# Welder_HMI.net
KiCad netlist of a schematic drawn in EAGLE
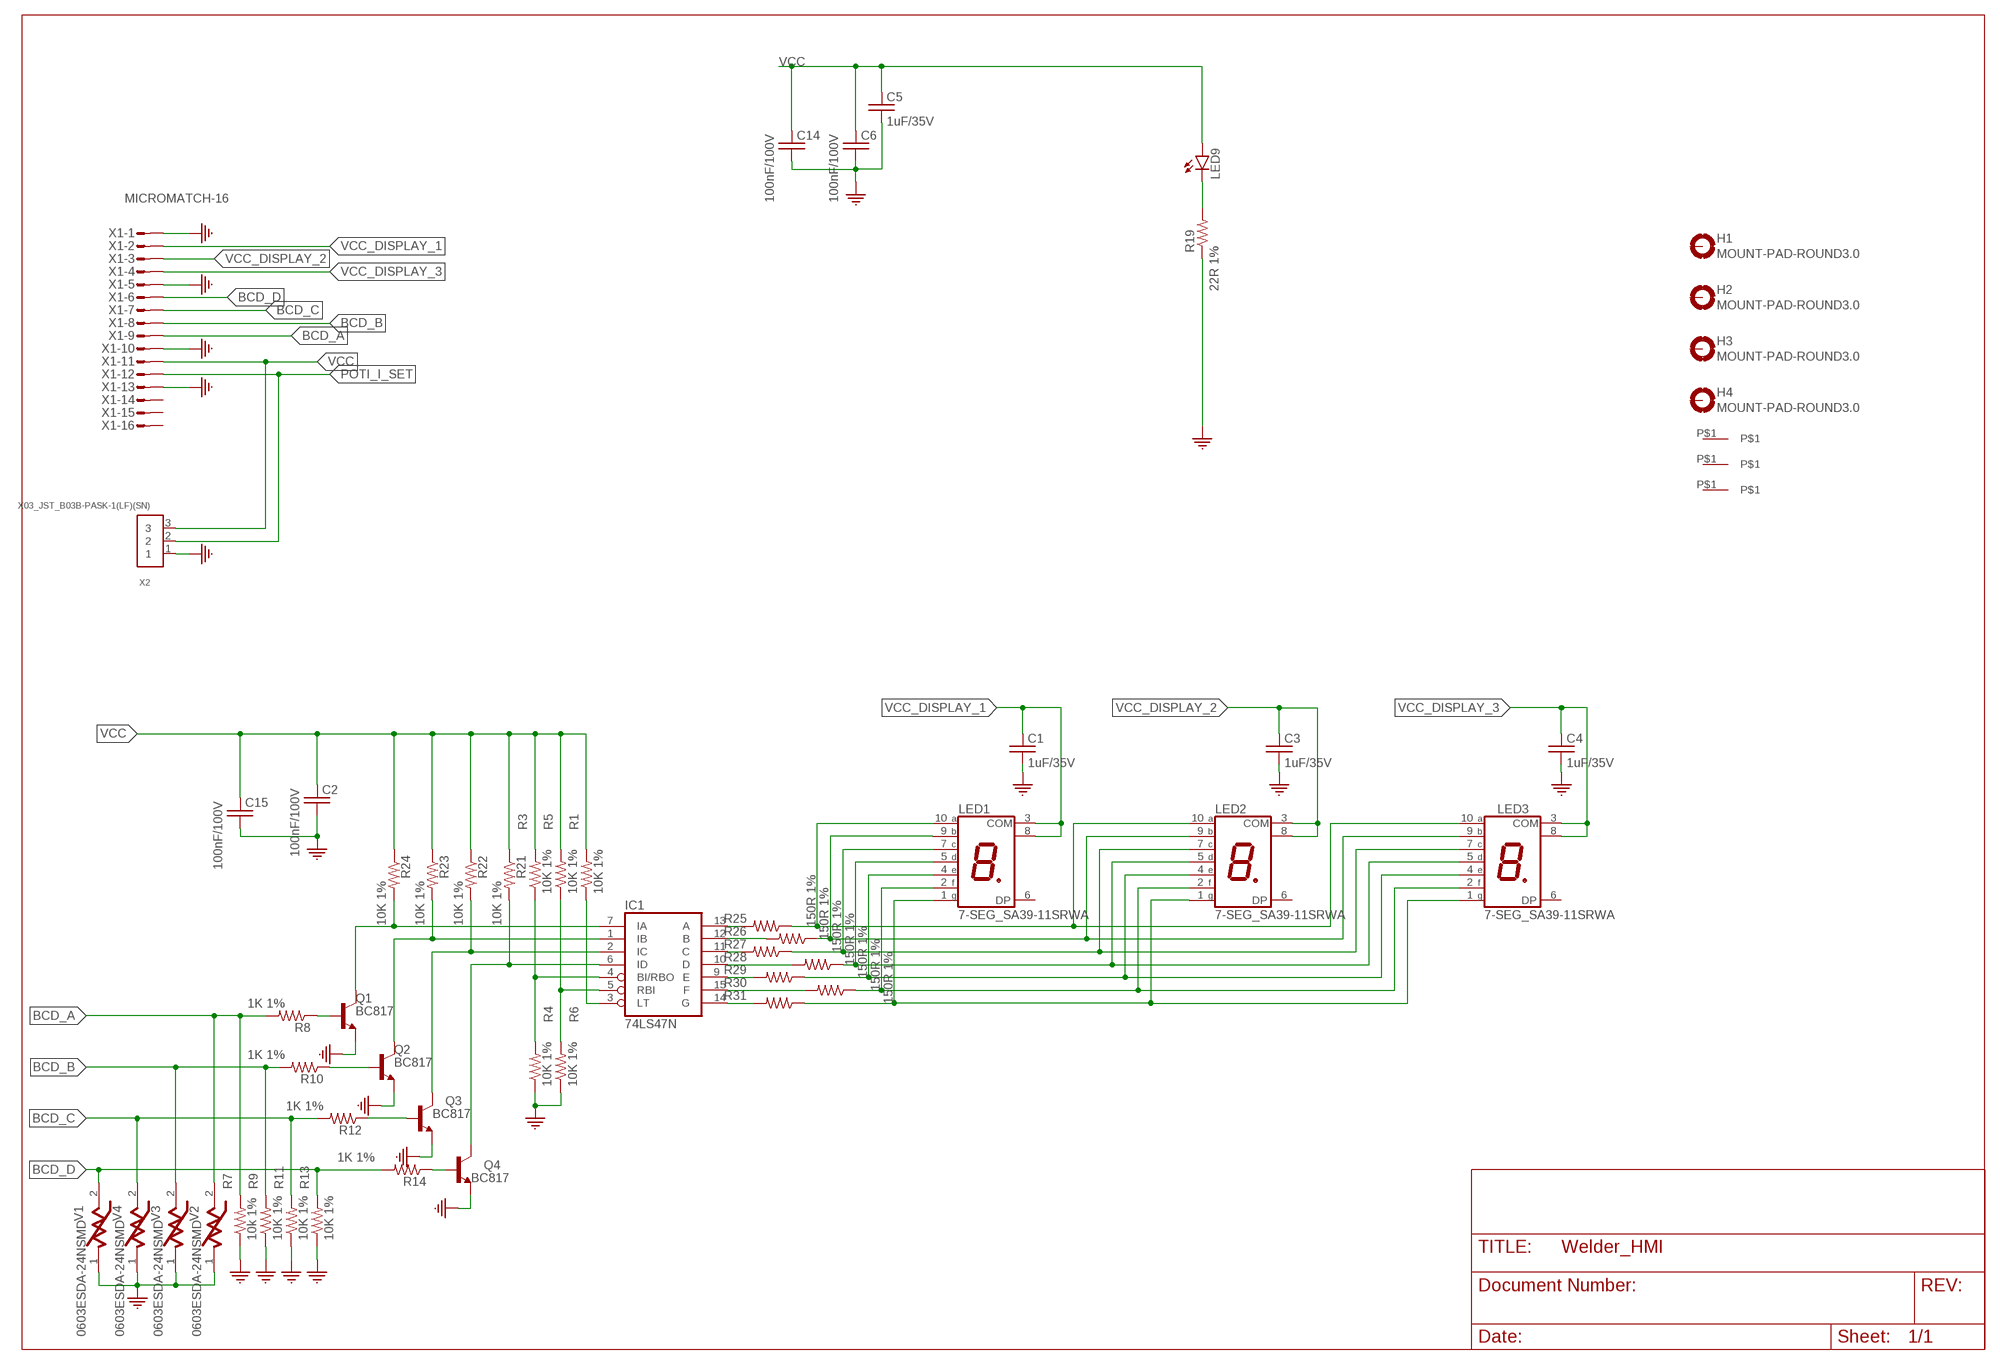
[diagram p0: schematic, sheet 1]

(export (version "E")
  (design (tool "Eeschema 10.0.6"))
  (components
    (comp (ref "C1")
      (value "1uF/35V")
      (footprint "eagle-import:EIA0603")
      (libsource (lib "eagle-import") (part "C_0603EIA0603"))
    )
    (comp (ref "C2")
      (value "100nF/100V")
      (footprint "eagle-import:EIA0603")
      (libsource (lib "eagle-import") (part "C_0603EIA0603"))
    )
    (comp (ref "C3")
      (value "1uF/35V")
      (footprint "eagle-import:EIA0603")
      (libsource (lib "eagle-import") (part "C_0603EIA0603"))
    )
    (comp (ref "C4")
      (value "1uF/35V")
      (footprint "eagle-import:EIA0603")
      (libsource (lib "eagle-import") (part "C_0603EIA0603"))
    )
    (comp (ref "C5")
      (value "1uF/35V")
      (footprint "eagle-import:EIA0603")
      (libsource (lib "eagle-import") (part "C_0603EIA0603"))
    )
    (comp (ref "C6")
      (value "100nF/100V")
      (footprint "eagle-import:EIA0603")
      (libsource (lib "eagle-import") (part "C_0603EIA0603"))
    )
    (comp (ref "C14")
      (value "100nF/100V")
      (footprint "eagle-import:EIA0603")
      (libsource (lib "eagle-import") (part "C_0603EIA0603"))
    )
    (comp (ref "C15")
      (value "100nF/100V")
      (footprint "eagle-import:EIA0603")
      (libsource (lib "eagle-import") (part "C_0603EIA0603"))
    )
    (comp (ref "FID1")
      (value "FIDUCIAL")
      (footprint "eagle-import:FIDUCIAL")
      (libsource (lib "eagle-import") (part "FIDUCIAL"))
    )
    (comp (ref "FID2")
      (value "FIDUCIAL")
      (footprint "eagle-import:FIDUCIAL")
      (libsource (lib "eagle-import") (part "FIDUCIAL"))
    )
    (comp (ref "FID3")
      (value "FIDUCIAL")
      (footprint "eagle-import:FIDUCIAL")
      (libsource (lib "eagle-import") (part "FIDUCIAL"))
    )
    (comp (ref "H1")
      (value "MOUNT-PAD-ROUND3.0")
      (footprint "eagle-import:3,0-PAD")
      (libsource (lib "eagle-import") (part "MOUNT-PAD-ROUND3.0"))
    )
    (comp (ref "H2")
      (value "MOUNT-PAD-ROUND3.0")
      (footprint "eagle-import:3,0-PAD")
      (libsource (lib "eagle-import") (part "MOUNT-PAD-ROUND3.0"))
    )
    (comp (ref "H3")
      (value "MOUNT-PAD-ROUND3.0")
      (footprint "eagle-import:3,0-PAD")
      (libsource (lib "eagle-import") (part "MOUNT-PAD-ROUND3.0"))
    )
    (comp (ref "H4")
      (value "MOUNT-PAD-ROUND3.0")
      (footprint "eagle-import:3,0-PAD")
      (libsource (lib "eagle-import") (part "MOUNT-PAD-ROUND3.0"))
    )
    (comp (ref "IC1")
      (value "74LS47N")
      (footprint "eagle-import:DIL16")
      (libsource (lib "eagle-import") (part "7447NLS"))
    )
    (comp (ref "LED1")
      (value "7-SEG_SA39-11SRWA")
      (footprint "eagle-import:SA39-11SRWA")
      (libsource (lib "eagle-import") (part "7-SEG_SA39-11SRWA"))
    )
    (comp (ref "LED2")
      (value "7-SEG_SA39-11SRWA")
      (footprint "eagle-import:SA39-11SRWA")
      (libsource (lib "eagle-import") (part "7-SEG_SA39-11SRWA"))
    )
    (comp (ref "LED3")
      (value "7-SEG_SA39-11SRWA")
      (footprint "eagle-import:SA39-11SRWA")
      (libsource (lib "eagle-import") (part "7-SEG_SA39-11SRWA"))
    )
    (comp (ref "LED9")
      (value "LED5MM")
      (footprint "eagle-import:LED5MM")
      (libsource (lib "eagle-import") (part "LED5MM"))
    )
    (comp (ref "Q1")
      (value "BC817")
      (footprint "eagle-import:SOT23")
      (fields (field (name "MFR") "NXP"))
      (libsource (lib "eagle-import") (part "BC817"))
    )
    (comp (ref "Q2")
      (value "BC817")
      (footprint "eagle-import:SOT23")
      (fields (field (name "MFR") "NXP"))
      (libsource (lib "eagle-import") (part "BC817"))
    )
    (comp (ref "Q3")
      (value "BC817")
      (footprint "eagle-import:SOT23")
      (fields (field (name "MFR") "NXP"))
      (libsource (lib "eagle-import") (part "BC817"))
    )
    (comp (ref "Q4")
      (value "BC817")
      (footprint "eagle-import:SOT23")
      (fields (field (name "MFR") "NXP"))
      (libsource (lib "eagle-import") (part "BC817"))
    )
    (comp (ref "R1")
      (value "10K 1%")
      (footprint "eagle-import:EIA0603")
      (libsource (lib "eagle-import") (part "R_0603"))
    )
    (comp (ref "R3")
      (value "10K 1%")
      (footprint "eagle-import:EIA0603")
      (libsource (lib "eagle-import") (part "R_0603"))
    )
    (comp (ref "R4")
      (value "10K 1%")
      (footprint "eagle-import:EIA0603")
      (libsource (lib "eagle-import") (part "R_0603"))
    )
    (comp (ref "R5")
      (value "10K 1%")
      (footprint "eagle-import:EIA0603")
      (libsource (lib "eagle-import") (part "R_0603"))
    )
    (comp (ref "R6")
      (value "10K 1%")
      (footprint "eagle-import:EIA0603")
      (libsource (lib "eagle-import") (part "R_0603"))
    )
    (comp (ref "R7")
      (value "10k 1%")
      (footprint "eagle-import:EIA0603")
      (libsource (lib "eagle-import") (part "R_0603"))
    )
    (comp (ref "R8")
      (value "1K 1%")
      (footprint "eagle-import:EIA0603")
      (libsource (lib "eagle-import") (part "R_0603"))
    )
    (comp (ref "R9")
      (value "10K 1%")
      (footprint "eagle-import:EIA0603")
      (libsource (lib "eagle-import") (part "R_0603"))
    )
    (comp (ref "R10")
      (value "1K 1%")
      (footprint "eagle-import:EIA0603")
      (libsource (lib "eagle-import") (part "R_0603"))
    )
    (comp (ref "R11")
      (value "10K 1%")
      (footprint "eagle-import:EIA0603")
      (libsource (lib "eagle-import") (part "R_0603"))
    )
    (comp (ref "R12")
      (value "1K 1%")
      (footprint "eagle-import:EIA0603")
      (libsource (lib "eagle-import") (part "R_0603"))
    )
    (comp (ref "R13")
      (value "10K 1%")
      (footprint "eagle-import:EIA0603")
      (libsource (lib "eagle-import") (part "R_0603"))
    )
    (comp (ref "R14")
      (value "1K 1%")
      (footprint "eagle-import:EIA0603")
      (libsource (lib "eagle-import") (part "R_0603"))
    )
    (comp (ref "R19")
      (value "22R 1%")
      (footprint "eagle-import:EIA1206")
      (libsource (lib "eagle-import") (part "R_1206EIA1206"))
    )
    (comp (ref "R21")
      (value "10K 1%")
      (footprint "eagle-import:EIA0603")
      (libsource (lib "eagle-import") (part "R_0603"))
    )
    (comp (ref "R22")
      (value "10K 1%")
      (footprint "eagle-import:EIA0603")
      (libsource (lib "eagle-import") (part "R_0603"))
    )
    (comp (ref "R23")
      (value "10K 1%")
      (footprint "eagle-import:EIA0603")
      (libsource (lib "eagle-import") (part "R_0603"))
    )
    (comp (ref "R24")
      (value "10K 1%")
      (footprint "eagle-import:EIA0603")
      (libsource (lib "eagle-import") (part "R_0603"))
    )
    (comp (ref "R25")
      (value "150R 1%")
      (footprint "eagle-import:EIA1206")
      (libsource (lib "eagle-import") (part "R_1206EIA1206"))
    )
    (comp (ref "R26")
      (value "150R 1%")
      (footprint "eagle-import:EIA1206")
      (libsource (lib "eagle-import") (part "R_1206EIA1206"))
    )
    (comp (ref "R27")
      (value "150R 1%")
      (footprint "eagle-import:EIA1206")
      (libsource (lib "eagle-import") (part "R_1206EIA1206"))
    )
    (comp (ref "R28")
      (value "150R 1%")
      (footprint "eagle-import:EIA1206")
      (libsource (lib "eagle-import") (part "R_1206EIA1206"))
    )
    (comp (ref "R29")
      (value "150R 1%")
      (footprint "eagle-import:EIA1206")
      (libsource (lib "eagle-import") (part "R_1206EIA1206"))
    )
    (comp (ref "R30")
      (value "150R 1%")
      (footprint "eagle-import:EIA1206")
      (libsource (lib "eagle-import") (part "R_1206EIA1206"))
    )
    (comp (ref "R31")
      (value "150R 1%")
      (footprint "eagle-import:EIA1206")
      (libsource (lib "eagle-import") (part "R_1206EIA1206"))
    )
    (comp (ref "V1")
      (value "0603ESDA-24NSMD")
      (footprint "eagle-import:EIA0603")
      (fields (field (name "MFR") "Bourns"))
      (libsource (lib "eagle-import") (part "0603ESDA-24NSMD"))
    )
    (comp (ref "V2")
      (value "0603ESDA-24NSMD")
      (footprint "eagle-import:EIA0603")
      (fields (field (name "MFR") "Bourns"))
      (libsource (lib "eagle-import") (part "0603ESDA-24NSMD"))
    )
    (comp (ref "V3")
      (value "0603ESDA-24NSMD")
      (footprint "eagle-import:EIA0603")
      (fields (field (name "MFR") "Bourns"))
      (libsource (lib "eagle-import") (part "0603ESDA-24NSMD"))
    )
    (comp (ref "V4")
      (value "0603ESDA-24NSMD")
      (footprint "eagle-import:EIA0603")
      (fields (field (name "MFR") "Bourns"))
      (libsource (lib "eagle-import") (part "0603ESDA-24NSMD"))
    )
    (comp (ref "X1")
      (value "MICROMATCH-16")
      (footprint "eagle-import:MICROMATCH-16")
      (fields (field (name "MF") "FARNELL") (field (name "MPN") "8-215464-6"))
      (libsource (lib "eagle-import") (part "MICROMATCH-16"))
    )
    (comp (ref "X2")
      (value "X03_JST_B03B-PASK-1(LF)(SN)")
      (footprint "eagle-import:X03_JST_B03B-PASK-1(LF)(SN)")
      (fields (field (name "MFR") "JST"))
      (libsource (lib "eagle-import") (part "X03_JST_B03B-PASK-1(LF)(SN)"))
    )
  )
  (nets
    (net (code "1") (name "BCD_A") (class "Default")
      (node (ref "R7") (pin "2") (pinfunction "2_2") (pintype "passive"))
      (node (ref "R8") (pin "2") (pinfunction "2_2") (pintype "passive"))
      (node (ref "V2") (pin "2") (pinfunction "2_2") (pintype "passive"))
      (node (ref "X1") (pin "9") (pinfunction "S_9") (pintype "passive"))
    )
    (net (code "2") (name "BCD_B") (class "Default")
      (node (ref "R10") (pin "2") (pinfunction "2_2") (pintype "passive"))
      (node (ref "R9") (pin "2") (pinfunction "2_2") (pintype "passive"))
      (node (ref "V3") (pin "2") (pinfunction "2_2") (pintype "passive"))
      (node (ref "X1") (pin "8") (pinfunction "S_8") (pintype "passive"))
    )
    (net (code "3") (name "BCD_C") (class "Default")
      (node (ref "R11") (pin "2") (pinfunction "2_2") (pintype "passive"))
      (node (ref "R12") (pin "2") (pinfunction "2_2") (pintype "passive"))
      (node (ref "V4") (pin "2") (pinfunction "2_2") (pintype "passive"))
      (node (ref "X1") (pin "7") (pinfunction "S_7") (pintype "passive"))
    )
    (net (code "4") (name "BCD_D") (class "Default")
      (node (ref "R13") (pin "2") (pinfunction "2_2") (pintype "passive"))
      (node (ref "R14") (pin "2") (pinfunction "2_2") (pintype "passive"))
      (node (ref "V1") (pin "2") (pinfunction "2_2") (pintype "passive"))
      (node (ref "X1") (pin "6") (pinfunction "S_6") (pintype "passive"))
    )
    (net (code "5") (name "GND") (class "Default")
      (node (ref "C1") (pin "2") (pinfunction "2_2") (pintype "passive"))
      (node (ref "C14") (pin "2") (pinfunction "2_2") (pintype "passive"))
      (node (ref "C15") (pin "2") (pinfunction "2_2") (pintype "passive"))
      (node (ref "C2") (pin "2") (pinfunction "2_2") (pintype "passive"))
      (node (ref "C3") (pin "2") (pinfunction "2_2") (pintype "passive"))
      (node (ref "C4") (pin "2") (pinfunction "2_2") (pintype "passive"))
      (node (ref "C5") (pin "2") (pinfunction "2_2") (pintype "passive"))
      (node (ref "C6") (pin "2") (pinfunction "2_2") (pintype "passive"))
      (node (ref "Q1") (pin "2") (pinfunction "E_2") (pintype "passive"))
      (node (ref "Q2") (pin "2") (pinfunction "E_2") (pintype "passive"))
      (node (ref "Q3") (pin "2") (pinfunction "E_2") (pintype "passive"))
      (node (ref "Q4") (pin "2") (pinfunction "E_2") (pintype "passive"))
      (node (ref "R11") (pin "1") (pinfunction "1_1") (pintype "passive"))
      (node (ref "R13") (pin "1") (pinfunction "1_1") (pintype "passive"))
      (node (ref "R19") (pin "1") (pinfunction "1_1") (pintype "passive"))
      (node (ref "R4") (pin "1") (pinfunction "1_1") (pintype "passive"))
      (node (ref "R6") (pin "1") (pinfunction "1_1") (pintype "passive"))
      (node (ref "R7") (pin "1") (pinfunction "1_1") (pintype "passive"))
      (node (ref "R9") (pin "1") (pinfunction "1_1") (pintype "passive"))
      (node (ref "V1") (pin "1") (pinfunction "1_1") (pintype "passive"))
      (node (ref "V2") (pin "1") (pinfunction "1_1") (pintype "passive"))
      (node (ref "V3") (pin "1") (pinfunction "1_1") (pintype "passive"))
      (node (ref "V4") (pin "1") (pinfunction "1_1") (pintype "passive"))
      (node (ref "X1") (pin "1") (pinfunction "S_1") (pintype "passive"))
      (node (ref "X1") (pin "10") (pinfunction "S_10") (pintype "passive"))
      (node (ref "X1") (pin "13") (pinfunction "S_13") (pintype "passive"))
      (node (ref "X1") (pin "5") (pinfunction "S_5") (pintype "passive"))
      (node (ref "X2") (pin "1") (pinfunction "1_1") (pintype "bidirectional"))
    )
    (net (code "6") (name "Net-(IC1A-A)") (class "Default")
      (node (ref "IC1") (pin "13") (pinfunction "A_13") (pintype "output"))
      (node (ref "R25") (pin "2") (pinfunction "2_2") (pintype "passive"))
    )
    (net (code "7") (name "Net-(IC1A-B)") (class "Default")
      (node (ref "IC1") (pin "12") (pinfunction "B_12") (pintype "output"))
      (node (ref "R26") (pin "2") (pinfunction "2_2") (pintype "passive"))
    )
    (net (code "8") (name "Net-(IC1A-BI{slash}RBO)") (class "Default")
      (node (ref "IC1") (pin "4") (pinfunction "BI/RBO_4") (pintype "input"))
      (node (ref "R3") (pin "1") (pinfunction "1_1") (pintype "passive"))
      (node (ref "R4") (pin "2") (pinfunction "2_2") (pintype "passive"))
    )
    (net (code "9") (name "Net-(IC1A-C)") (class "Default")
      (node (ref "IC1") (pin "11") (pinfunction "C_11") (pintype "output"))
      (node (ref "R27") (pin "2") (pinfunction "2_2") (pintype "passive"))
    )
    (net (code "10") (name "Net-(IC1A-D)") (class "Default")
      (node (ref "IC1") (pin "10") (pinfunction "D_10") (pintype "output"))
      (node (ref "R28") (pin "2") (pinfunction "2_2") (pintype "passive"))
    )
    (net (code "11") (name "Net-(IC1A-E)") (class "Default")
      (node (ref "IC1") (pin "9") (pinfunction "E_9") (pintype "output"))
      (node (ref "R29") (pin "2") (pinfunction "2_2") (pintype "passive"))
    )
    (net (code "12") (name "Net-(IC1A-F)") (class "Default")
      (node (ref "IC1") (pin "15") (pinfunction "F_15") (pintype "output"))
      (node (ref "R30") (pin "2") (pinfunction "2_2") (pintype "passive"))
    )
    (net (code "13") (name "Net-(IC1A-G)") (class "Default")
      (node (ref "IC1") (pin "14") (pinfunction "G_14") (pintype "output"))
      (node (ref "R31") (pin "2") (pinfunction "2_2") (pintype "passive"))
    )
    (net (code "14") (name "Net-(IC1A-IA)") (class "Default")
      (node (ref "IC1") (pin "7") (pinfunction "IA_7") (pintype "input"))
      (node (ref "Q1") (pin "3") (pinfunction "C_3") (pintype "passive"))
      (node (ref "R24") (pin "2") (pinfunction "2_2") (pintype "passive"))
    )
    (net (code "15") (name "Net-(IC1A-IB)") (class "Default")
      (node (ref "IC1") (pin "1") (pinfunction "IB_1") (pintype "input"))
      (node (ref "Q2") (pin "3") (pinfunction "C_3") (pintype "passive"))
      (node (ref "R23") (pin "2") (pinfunction "2_2") (pintype "passive"))
    )
    (net (code "16") (name "Net-(IC1A-IC)") (class "Default")
      (node (ref "IC1") (pin "2") (pinfunction "IC_2") (pintype "input"))
      (node (ref "Q3") (pin "3") (pinfunction "C_3") (pintype "passive"))
      (node (ref "R22") (pin "2") (pinfunction "2_2") (pintype "passive"))
    )
    (net (code "17") (name "Net-(IC1A-ID)") (class "Default")
      (node (ref "IC1") (pin "6") (pinfunction "ID_6") (pintype "input"))
      (node (ref "Q4") (pin "3") (pinfunction "C_3") (pintype "passive"))
      (node (ref "R21") (pin "2") (pinfunction "2_2") (pintype "passive"))
    )
    (net (code "18") (name "Net-(IC1A-LT)") (class "Default")
      (node (ref "IC1") (pin "3") (pinfunction "LT_3") (pintype "input"))
      (node (ref "R1") (pin "1") (pinfunction "1_1") (pintype "passive"))
    )
    (net (code "19") (name "Net-(IC1A-RBI)") (class "Default")
      (node (ref "IC1") (pin "5") (pinfunction "RBI_5") (pintype "input"))
      (node (ref "R5") (pin "1") (pinfunction "1_1") (pintype "passive"))
      (node (ref "R6") (pin "2") (pinfunction "2_2") (pintype "passive"))
    )
    (net (code "20") (name "Net-(LED1-A)") (class "Default")
      (node (ref "LED1") (pin "10") (pinfunction "A_10") (pintype "passive"))
      (node (ref "LED2") (pin "10") (pinfunction "A_10") (pintype "passive"))
      (node (ref "LED3") (pin "10") (pinfunction "A_10") (pintype "passive"))
      (node (ref "R25") (pin "1") (pinfunction "1_1") (pintype "passive"))
    )
    (net (code "21") (name "Net-(LED1-B)") (class "Default")
      (node (ref "LED1") (pin "9") (pinfunction "B_9") (pintype "passive"))
      (node (ref "LED2") (pin "9") (pinfunction "B_9") (pintype "passive"))
      (node (ref "LED3") (pin "9") (pinfunction "B_9") (pintype "passive"))
      (node (ref "R26") (pin "1") (pinfunction "1_1") (pintype "passive"))
    )
    (net (code "22") (name "Net-(LED1-C)") (class "Default")
      (node (ref "LED1") (pin "7") (pinfunction "C_7") (pintype "passive"))
      (node (ref "LED2") (pin "7") (pinfunction "C_7") (pintype "passive"))
      (node (ref "LED3") (pin "7") (pinfunction "C_7") (pintype "passive"))
      (node (ref "R27") (pin "1") (pinfunction "1_1") (pintype "passive"))
    )
    (net (code "23") (name "Net-(LED1-D)") (class "Default")
      (node (ref "LED1") (pin "5") (pinfunction "D_5") (pintype "passive"))
      (node (ref "LED2") (pin "5") (pinfunction "D_5") (pintype "passive"))
      (node (ref "LED3") (pin "5") (pinfunction "D_5") (pintype "passive"))
      (node (ref "R28") (pin "1") (pinfunction "1_1") (pintype "passive"))
    )
    (net (code "24") (name "Net-(LED1-E)") (class "Default")
      (node (ref "LED1") (pin "4") (pinfunction "E_4") (pintype "passive"))
      (node (ref "LED2") (pin "4") (pinfunction "E_4") (pintype "passive"))
      (node (ref "LED3") (pin "4") (pinfunction "E_4") (pintype "passive"))
      (node (ref "R29") (pin "1") (pinfunction "1_1") (pintype "passive"))
    )
    (net (code "25") (name "Net-(LED1-F)") (class "Default")
      (node (ref "LED1") (pin "2") (pinfunction "F_2") (pintype "passive"))
      (node (ref "LED2") (pin "2") (pinfunction "F_2") (pintype "passive"))
      (node (ref "LED3") (pin "2") (pinfunction "F_2") (pintype "passive"))
      (node (ref "R30") (pin "1") (pinfunction "1_1") (pintype "passive"))
    )
    (net (code "26") (name "Net-(LED1-G)") (class "Default")
      (node (ref "LED1") (pin "1") (pinfunction "G_1") (pintype "passive"))
      (node (ref "LED2") (pin "1") (pinfunction "G_1") (pintype "passive"))
      (node (ref "LED3") (pin "1") (pinfunction "G_1") (pintype "passive"))
      (node (ref "R31") (pin "1") (pinfunction "1_1") (pintype "passive"))
    )
    (net (code "27") (name "Net-(LED9-C)") (class "Default")
      (node (ref "LED9") (pin "K") (pinfunction "C_K") (pintype "passive"))
      (node (ref "R19") (pin "2") (pinfunction "2_2") (pintype "passive"))
    )
    (net (code "28") (name "Net-(Q1-B)") (class "Default")
      (node (ref "Q1") (pin "1") (pinfunction "B_1") (pintype "passive"))
      (node (ref "R8") (pin "1") (pinfunction "1_1") (pintype "passive"))
    )
    (net (code "29") (name "Net-(Q2-B)") (class "Default")
      (node (ref "Q2") (pin "1") (pinfunction "B_1") (pintype "passive"))
      (node (ref "R10") (pin "1") (pinfunction "1_1") (pintype "passive"))
    )
    (net (code "30") (name "Net-(Q3-B)") (class "Default")
      (node (ref "Q3") (pin "1") (pinfunction "B_1") (pintype "passive"))
      (node (ref "R12") (pin "1") (pinfunction "1_1") (pintype "passive"))
    )
    (net (code "31") (name "Net-(Q4-B)") (class "Default")
      (node (ref "Q4") (pin "1") (pinfunction "B_1") (pintype "passive"))
      (node (ref "R14") (pin "1") (pinfunction "1_1") (pintype "passive"))
    )
    (net (code "32") (name "POTI_I_SET") (class "Default")
      (node (ref "X1") (pin "12") (pinfunction "S_12") (pintype "passive"))
      (node (ref "X2") (pin "2") (pinfunction "2_2") (pintype "bidirectional"))
    )
    (net (code "33") (name "VCC") (class "Default")
      (node (ref "C14") (pin "1") (pinfunction "1_1") (pintype "passive"))
      (node (ref "C15") (pin "1") (pinfunction "1_1") (pintype "passive"))
      (node (ref "C2") (pin "1") (pinfunction "1_1") (pintype "passive"))
      (node (ref "C5") (pin "1") (pinfunction "1_1") (pintype "passive"))
      (node (ref "C6") (pin "1") (pinfunction "1_1") (pintype "passive"))
      (node (ref "LED9") (pin "A") (pinfunction "A_A") (pintype "passive"))
      (node (ref "R1") (pin "2") (pinfunction "2_2") (pintype "passive"))
      (node (ref "R21") (pin "1") (pinfunction "1_1") (pintype "passive"))
      (node (ref "R22") (pin "1") (pinfunction "1_1") (pintype "passive"))
      (node (ref "R23") (pin "1") (pinfunction "1_1") (pintype "passive"))
      (node (ref "R24") (pin "1") (pinfunction "1_1") (pintype "passive"))
      (node (ref "R3") (pin "2") (pinfunction "2_2") (pintype "passive"))
      (node (ref "R5") (pin "2") (pinfunction "2_2") (pintype "passive"))
      (node (ref "X1") (pin "11") (pinfunction "S_11") (pintype "passive"))
      (node (ref "X2") (pin "3") (pinfunction "3_3") (pintype "bidirectional"))
    )
    (net (code "34") (name "VCC_DISPLAY_1") (class "Default")
      (node (ref "C1") (pin "1") (pinfunction "1_1") (pintype "passive"))
      (node (ref "LED1") (pin "3") (pinfunction "COM_3") (pintype "passive"))
      (node (ref "LED1") (pin "8") (pinfunction "COM_8") (pintype "passive"))
      (node (ref "X1") (pin "2") (pinfunction "S_2") (pintype "passive"))
    )
    (net (code "35") (name "VCC_DISPLAY_2") (class "Default")
      (node (ref "C3") (pin "1") (pinfunction "1_1") (pintype "passive"))
      (node (ref "LED2") (pin "3") (pinfunction "COM_3") (pintype "passive"))
      (node (ref "LED2") (pin "8") (pinfunction "COM_8") (pintype "passive"))
      (node (ref "X1") (pin "3") (pinfunction "S_3") (pintype "passive"))
    )
    (net (code "36") (name "VCC_DISPLAY_3") (class "Default")
      (node (ref "C4") (pin "1") (pinfunction "1_1") (pintype "passive"))
      (node (ref "LED3") (pin "3") (pinfunction "COM_3") (pintype "passive"))
      (node (ref "LED3") (pin "8") (pinfunction "COM_8") (pintype "passive"))
      (node (ref "X1") (pin "4") (pinfunction "S_4") (pintype "passive"))
    )
    (net (code "37") (name "unconnected-(FID1-PadP$1)") (class "Default")
      (node (ref "FID1") (pin "P$1") (pinfunction "P$1_P$1") (pintype "bidirectional"))
    )
    (net (code "38") (name "unconnected-(FID2-PadP$1)") (class "Default")
      (node (ref "FID2") (pin "P$1") (pinfunction "P$1_P$1") (pintype "bidirectional"))
    )
    (net (code "39") (name "unconnected-(FID3-PadP$1)") (class "Default")
      (node (ref "FID3") (pin "P$1") (pinfunction "P$1_P$1") (pintype "bidirectional"))
    )
    (net (code "40") (name "unconnected-(H1-MOUNT-PadB3,0)") (class "Default")
      (node (ref "H1") (pin "B3,0") (pinfunction "MOUNT_B3,0") (pintype "passive"))
    )
    (net (code "41") (name "unconnected-(H2-MOUNT-PadB3,0)") (class "Default")
      (node (ref "H2") (pin "B3,0") (pinfunction "MOUNT_B3,0") (pintype "passive"))
    )
    (net (code "42") (name "unconnected-(H3-MOUNT-PadB3,0)") (class "Default")
      (node (ref "H3") (pin "B3,0") (pinfunction "MOUNT_B3,0") (pintype "passive"))
    )
    (net (code "43") (name "unconnected-(H4-MOUNT-PadB3,0)") (class "Default")
      (node (ref "H4") (pin "B3,0") (pinfunction "MOUNT_B3,0") (pintype "passive"))
    )
    (net (code "44") (name "unconnected-(LED1-DP-Pad6)") (class "Default")
      (node (ref "LED1") (pin "6") (pinfunction "DP_6") (pintype "passive"))
    )
    (net (code "45") (name "unconnected-(LED2-DP-Pad6)") (class "Default")
      (node (ref "LED2") (pin "6") (pinfunction "DP_6") (pintype "passive"))
    )
    (net (code "46") (name "unconnected-(LED3-DP-Pad6)") (class "Default")
      (node (ref "LED3") (pin "6") (pinfunction "DP_6") (pintype "passive"))
    )
    (net (code "47") (name "unconnected-(X1F-S-Pad14)") (class "Default")
      (node (ref "X1") (pin "14") (pinfunction "S_14") (pintype "passive"))
    )
    (net (code "48") (name "unconnected-(X1G-S-Pad15)") (class "Default")
      (node (ref "X1") (pin "15") (pinfunction "S_15") (pintype "passive"))
    )
    (net (code "49") (name "unconnected-(X1H-S-Pad16)") (class "Default")
      (node (ref "X1") (pin "16") (pinfunction "S_16") (pintype "passive"))
    )
  )
)
